# FogMachineTimer_revB.net
KiCad netlist of a schematic drawn in EAGLE
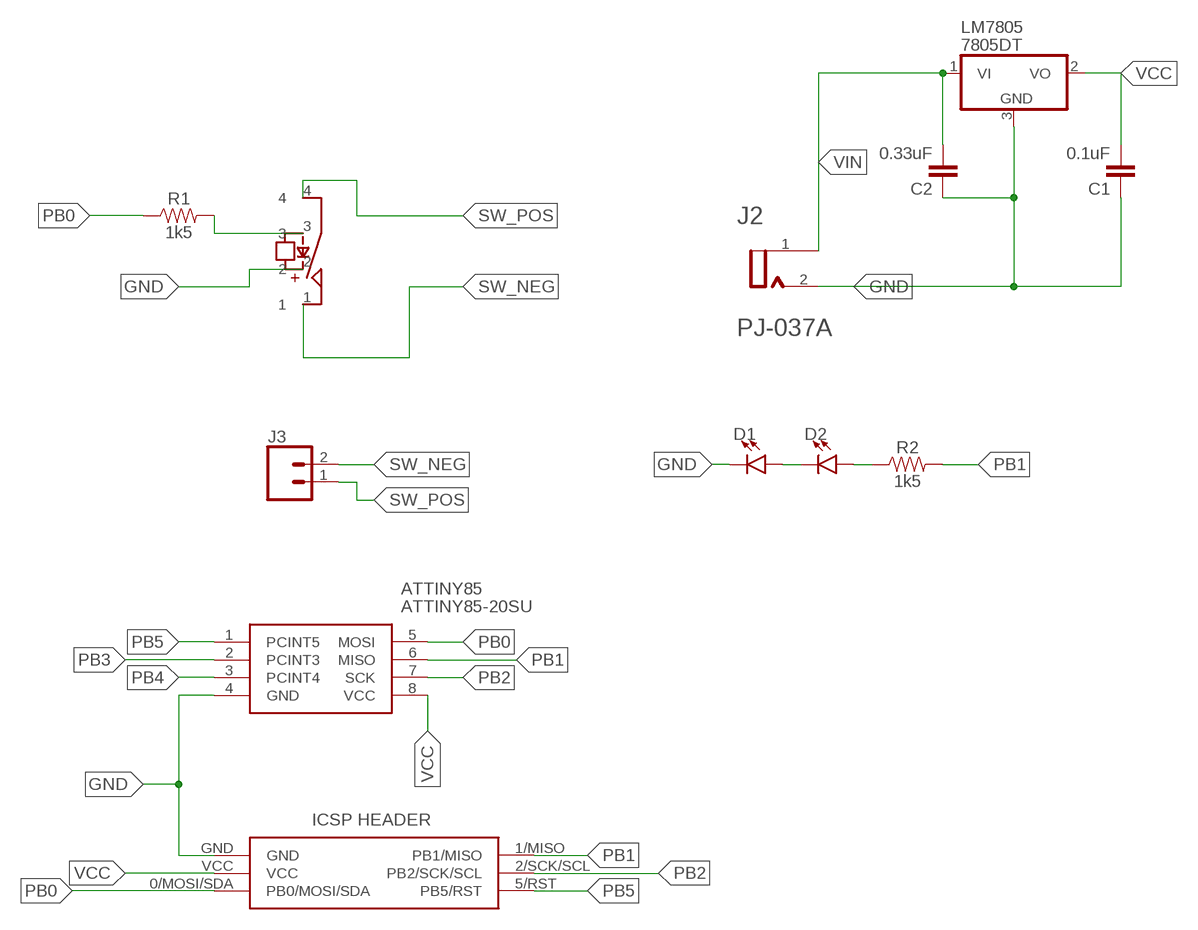
[diagram p0: schematic, sheet 1]

(export (version "E")
  (design (tool "Eeschema 10.0.6"))
  (components
    (comp (ref "ATTINY85")
      (value "ATTINY85-20SU")
      (footprint "eagle-import:SOT127P798X216-8N")
      (fields (field (name "RS_PART_NUMBER") "1331674"))
      (libsource (lib "eagle-import") (part "ATTINY85-20SU"))
    )
    (comp (ref "C1")
      (value "0.1uF")
      (footprint "eagle-import:0603")
      (libsource (lib "eagle-import") (part "0.1UF-0603-25V-5%"))
    )
    (comp (ref "C2")
      (value "0.33uF")
      (footprint "eagle-import:0603")
      (libsource (lib "eagle-import") (part "0.1UF-0603-25V-5%"))
    )
    (comp (ref "D1")
      (value "LED1206")
      (footprint "eagle-import:LED-1206")
      (libsource (lib "eagle-import") (part "LED1206"))
    )
    (comp (ref "D2")
      (value "LED1206")
      (footprint "eagle-import:LED-1206")
      (libsource (lib "eagle-import") (part "LED1206"))
    )
    (comp (ref "J1")
      (value "M20-9980346")
      (footprint "eagle-import:HDRV6W64P254_2X3_762X508X868P")
      (fields (field (name "RS_PART_NUMBER") "7457046P"))
      (libsource (lib "eagle-import") (part "M20-9980346"))
    )
    (comp (ref "J2")
      (value "CUI_PJ-037ACUI_PJ-037A_0_0")
      (footprint "eagle-import:CUI_PJ-037A_0")
      (fields
        (field (name "DIGIKEY_PART_NUMBER") "CP-037A-ND")
        (field (name "MF") "CUI")
        (field (name "MOUSER_PART_NUMBER") "490-PJ-037A")
      )
      (libsource (lib "eagle-import") (part "CUI_PJ-037ACUI_PJ-037A_0_0"))
    )
    (comp (ref "J3")
      (value "CONN_02")
      (footprint "eagle-import:1X02")
      (libsource (lib "eagle-import") (part "CONN_02"))
    )
    (comp (ref "LM7805")
      (value "7805DT")
      (footprint "eagle-import:TO252")
      (libsource (lib "eagle-import") (part "78DT05"))
    )
    (comp (ref "R1")
      (value "1k5")
      (footprint "eagle-import:0603")
      (libsource (lib "eagle-import") (part "1KOHM-0603-1/10W-1%"))
    )
    (comp (ref "R2")
      (value "1k5")
      (footprint "eagle-import:0603")
      (libsource (lib "eagle-import") (part "1KOHM-0603-1/10W-1%"))
    )
    (comp (ref "RELAY")
      (value "HE3621A0510")
      (footprint "eagle-import:HE3621A0510")
      (libsource (lib "eagle-import") (part "HE3621A0510"))
    )
  )
  (nets
    (net (code "1") (name "GND") (class "Default")
      (node (ref "ATTINY85") (pin "4") (pinfunction "GND_4") (pintype "power_in"))
      (node (ref "C1") (pin "1") (pinfunction "1_1") (pintype "passive"))
      (node (ref "C2") (pin "1") (pinfunction "1_1") (pintype "passive"))
      (node (ref "D1") (pin "C") (pinfunction "C_C") (pintype "passive"))
      (node (ref "J1") (pin "GND") (pinfunction "GND_GND") (pintype "bidirectional"))
      (node (ref "J2") (pin "2") (pinfunction "2_2") (pintype "bidirectional"))
      (node (ref "LM7805") (pin "3") (pinfunction "GND_3") (pintype "passive"))
      (node (ref "RELAY") (pin "2") (pinfunction "2_2") (pintype "bidirectional"))
    )
    (net (code "2") (name "Net-(D1-PadA)") (class "Default")
      (node (ref "D1") (pin "A") (pinfunction "A_A") (pintype "passive"))
      (node (ref "D2") (pin "C") (pinfunction "C_C") (pintype "passive"))
    )
    (net (code "3") (name "Net-(D2-PadA)") (class "Default")
      (node (ref "D2") (pin "A") (pinfunction "A_A") (pintype "passive"))
      (node (ref "R2") (pin "1") (pinfunction "1_1") (pintype "passive"))
    )
    (net (code "4") (name "Net-(R1-Pad2)") (class "Default")
      (node (ref "R1") (pin "2") (pinfunction "2_2") (pintype "passive"))
      (node (ref "RELAY") (pin "3") (pinfunction "3_3") (pintype "bidirectional"))
    )
    (net (code "5") (name "PB0") (class "Default")
      (node (ref "ATTINY85") (pin "5") (pinfunction "MOSI_5") (pintype "bidirectional"))
      (node (ref "J1") (pin "0/MOSI/SDA") (pinfunction "PB0/MOSI/SDA_0/MOSI/SDA") (pintype "bidirectional"))
      (node (ref "R1") (pin "1") (pinfunction "1_1") (pintype "passive"))
    )
    (net (code "6") (name "PB1") (class "Default")
      (node (ref "ATTINY85") (pin "6") (pinfunction "MISO_6") (pintype "bidirectional"))
      (node (ref "J1") (pin "1/MISO") (pinfunction "PB1/MISO_1/MISO") (pintype "bidirectional"))
      (node (ref "R2") (pin "2") (pinfunction "2_2") (pintype "passive"))
    )
    (net (code "7") (name "PB2") (class "Default")
      (node (ref "ATTINY85") (pin "7") (pinfunction "SCK_7") (pintype "bidirectional"))
      (node (ref "J1") (pin "2/SCK/SCL") (pinfunction "PB2/SCK/SCL_2/SCK/SCL") (pintype "bidirectional"))
    )
    (net (code "8") (name "PB3") (class "Default")
      (node (ref "ATTINY85") (pin "2") (pinfunction "PCINT3_2") (pintype "bidirectional"))
    )
    (net (code "9") (name "PB4") (class "Default")
      (node (ref "ATTINY85") (pin "3") (pinfunction "PCINT4_3") (pintype "bidirectional"))
    )
    (net (code "10") (name "PB5") (class "Default")
      (node (ref "ATTINY85") (pin "1") (pinfunction "PCINT5_1") (pintype "bidirectional"))
      (node (ref "J1") (pin "5/RST") (pinfunction "PB5/RST_5/RST") (pintype "bidirectional"))
    )
    (net (code "11") (name "SW_NEG") (class "Default")
      (node (ref "J3") (pin "2") (pinfunction "2_2") (pintype "passive"))
      (node (ref "RELAY") (pin "1") (pinfunction "1_1") (pintype "bidirectional"))
    )
    (net (code "12") (name "SW_POS") (class "Default")
      (node (ref "J3") (pin "1") (pinfunction "1_1") (pintype "passive"))
      (node (ref "RELAY") (pin "4") (pinfunction "4_4") (pintype "bidirectional"))
    )
    (net (code "13") (name "VCC") (class "Default")
      (node (ref "ATTINY85") (pin "8") (pinfunction "VCC_8") (pintype "power_in"))
      (node (ref "C1") (pin "2") (pinfunction "2_2") (pintype "passive"))
      (node (ref "J1") (pin "VCC") (pinfunction "VCC_VCC") (pintype "bidirectional"))
      (node (ref "LM7805") (pin "2") (pinfunction "VO_2") (pintype "passive"))
    )
    (net (code "14") (name "VIN") (class "Default")
      (node (ref "C2") (pin "2") (pinfunction "2_2") (pintype "passive"))
      (node (ref "J2") (pin "1") (pinfunction "1_1") (pintype "bidirectional"))
      (node (ref "LM7805") (pin "1") (pinfunction "VI_1") (pintype "input"))
    )
  )
)
